# DM1097_JTAG.net
KiCad netlist of a schematic drawn in Altium Designer
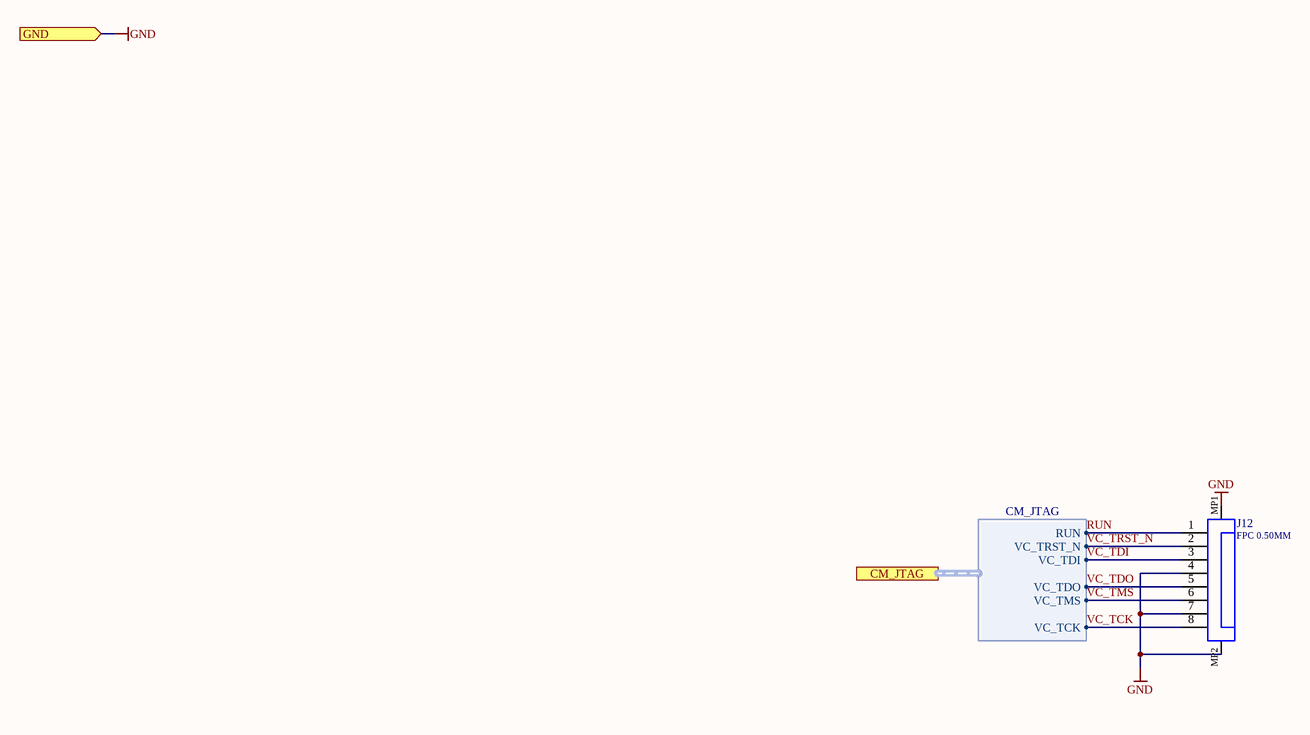
[diagram p0: DM1097_JTAG.SchDoc]

(export (version "E")
  (design (tool "Eeschema 10.0.6"))
  (components
    (comp (ref "J12")
      (value "FPC 0.50MM")
      (footprint "LuxonisMaster:68710814522")
      (libsource (lib "LuxonisMaster") (part "68710814522"))
    )
  )
  (nets
    (net (code "2") (name "/RUN") (class "Default")
      (node (ref "J12") (pin "1") (pinfunction "1_1") (pintype "passive"))
    )
    (net (code "3") (name "/VC_TCK") (class "Default")
      (node (ref "J12") (pin "8") (pinfunction "8_8") (pintype "passive"))
    )
    (net (code "4") (name "/VC_TDI") (class "Default")
      (node (ref "J12") (pin "3") (pinfunction "3_3") (pintype "passive"))
    )
    (net (code "5") (name "/VC_TDO") (class "Default")
      (node (ref "J12") (pin "5") (pinfunction "5_5") (pintype "passive"))
    )
    (net (code "6") (name "/VC_TMS") (class "Default")
      (node (ref "J12") (pin "6") (pinfunction "6_6") (pintype "passive"))
    )
    (net (code "7") (name "/VC_TRST_N") (class "Default")
      (node (ref "J12") (pin "2") (pinfunction "2_2") (pintype "passive"))
    )
    (net (code "9") (name "GND") (class "Default")
      (node (ref "J12") (pin "4") (pinfunction "4_4") (pintype "passive"))
      (node (ref "J12") (pin "7") (pinfunction "7_7") (pintype "passive"))
      (node (ref "J12") (pin "MP1") (pinfunction "MP1_MP1") (pintype "passive"))
      (node (ref "J12") (pin "MP2") (pinfunction "MP2_MP2") (pintype "passive"))
    )
  )
)
